# ARE_adaptadora_PIC_28pin.net
KiCad netlist of a schematic drawn in EAGLE
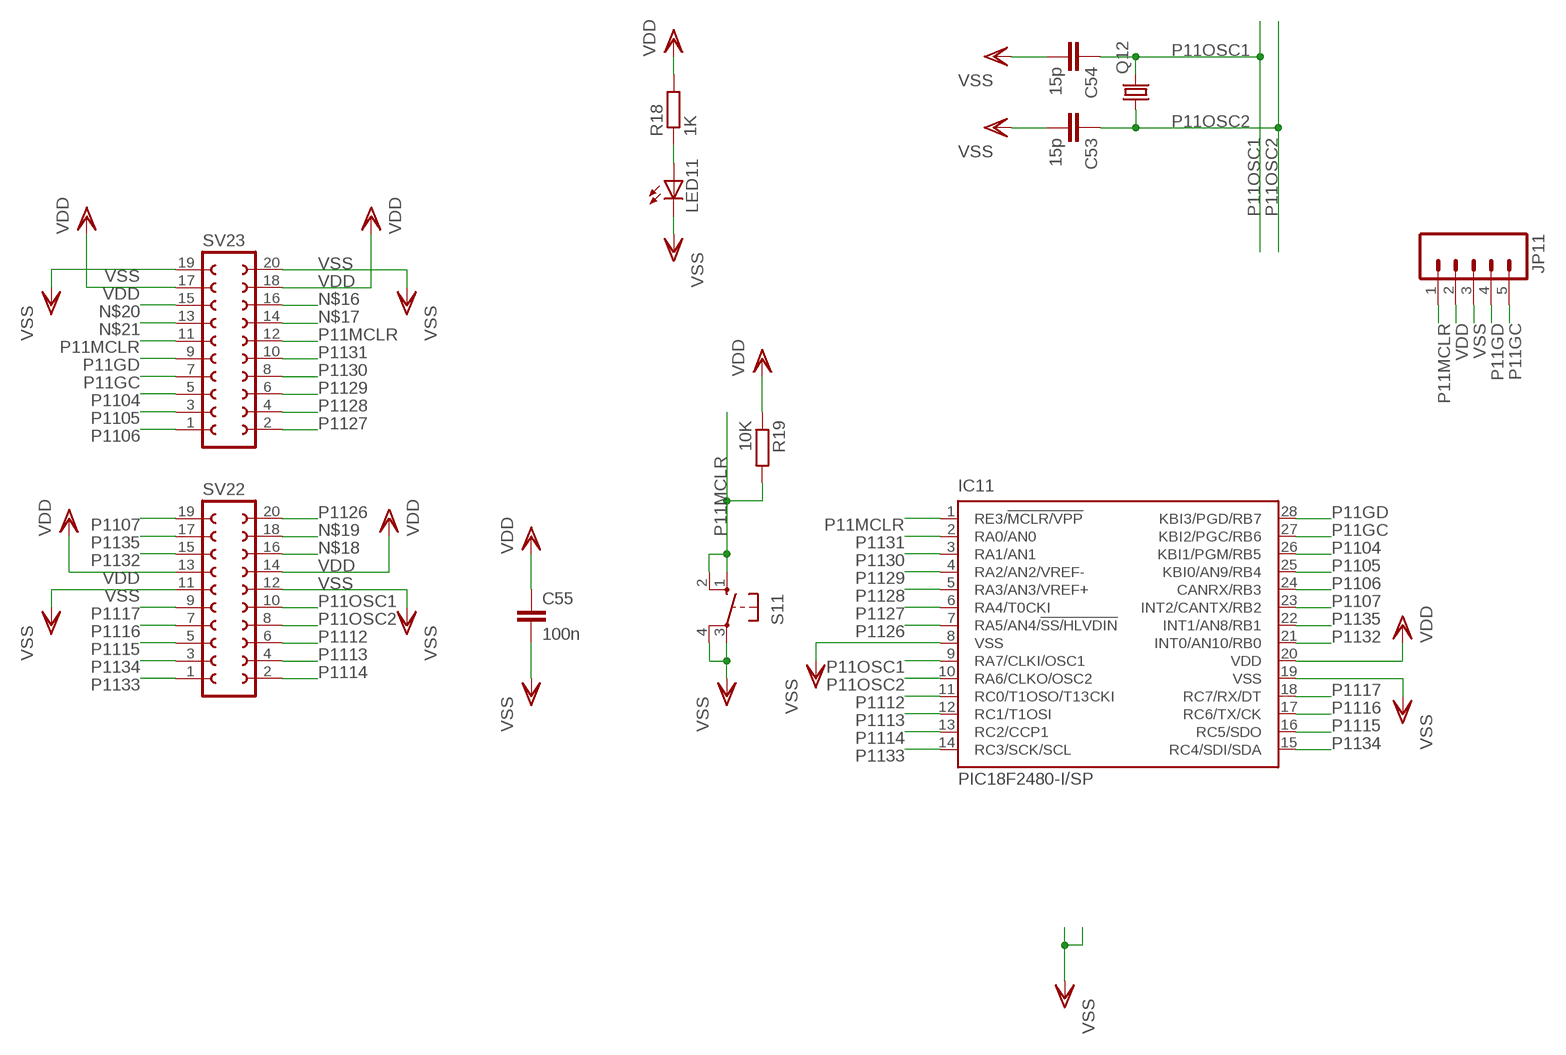
[diagram p0: schematic, sheet 1]

(export (version "E")
  (design (tool "Eeschema 10.0.6"))
  (components
    (comp (ref "C53")
      (value "15p")
      (footprint "eagle-import:C0805")
      (libsource (lib "eagle-import") (part "C-EUC0805"))
    )
    (comp (ref "C54")
      (value "15p")
      (footprint "eagle-import:C0805")
      (libsource (lib "eagle-import") (part "C-EUC0805"))
    )
    (comp (ref "C55")
      (value "100n")
      (footprint "eagle-import:C0805")
      (libsource (lib "eagle-import") (part "C-EUC0805"))
    )
    (comp (ref "IC11")
      (value "PIC18F2480-I/SP")
      (footprint "eagle-import:DIL28-3")
      (fields (field (name "MF") "MICROCHIP"))
      (libsource (lib "eagle-import") (part "PIC18F280-I/SP4"))
    )
    (comp (ref "JP11")
      (value "M05PTH")
      (footprint "eagle-import:1X05")
      (libsource (lib "eagle-import") (part "M05PTH"))
    )
    (comp (ref "LED11")
      (value "LED3MM")
      (footprint "eagle-import:LED3MM")
      (libsource (lib "eagle-import") (part "LED3MM"))
    )
    (comp (ref "Q12")
      (value "CRYSTALHC18U-V")
      (footprint "eagle-import:HC18U-V")
      (libsource (lib "eagle-import") (part "CRYSTALHC18U-V"))
    )
    (comp (ref "R18")
      (value "1K")
      (footprint "eagle-import:R0805")
      (libsource (lib "eagle-import") (part "R-EU_R0805"))
    )
    (comp (ref "R19")
      (value "10K")
      (footprint "eagle-import:R0805")
      (libsource (lib "eagle-import") (part "R-EU_R0805"))
    )
    (comp (ref "S11")
      (value "10-XX")
      (footprint "eagle-import:B3F-10XX")
      (fields
        (field (name "MPN") "B3F-1000")
        (field (name "MPN_1") "B3F-1000")
        (field (name "OC_FARNELL") "176432")
        (field (name "OC_NEWARK") "36M3542")
      )
      (libsource (lib "eagle-import") (part "10-XX"))
    )
    (comp (ref "SV22")
      (value "FE10-2W")
      (footprint "eagle-import:FE10-2W")
      (libsource (lib "eagle-import") (part "FE10-2W"))
    )
    (comp (ref "SV23")
      (value "FE10-2W")
      (footprint "eagle-import:FE10-2W")
      (fields (field (name "OC_FARNELL") "unknown") (field (name "OC_NEWARK") "unknown"))
      (libsource (lib "eagle-import") (part "FE10-2W"))
    )
  )
  (nets
    (net (code "1") (name "/N$16") (class "Default")
      (node (ref "SV23") (pin "16") (pinfunction "16_16") (pintype "passive"))
    )
    (net (code "2") (name "/N$17") (class "Default")
      (node (ref "SV23") (pin "14") (pinfunction "14_14") (pintype "passive"))
    )
    (net (code "3") (name "/N$18") (class "Default")
      (node (ref "SV22") (pin "16") (pinfunction "16_16") (pintype "passive"))
    )
    (net (code "4") (name "/N$19") (class "Default")
      (node (ref "SV22") (pin "18") (pinfunction "18_18") (pintype "passive"))
    )
    (net (code "5") (name "/N$20") (class "Default")
      (node (ref "SV23") (pin "15") (pinfunction "15_15") (pintype "passive"))
    )
    (net (code "6") (name "/N$21") (class "Default")
      (node (ref "SV23") (pin "13") (pinfunction "13_13") (pintype "passive"))
    )
    (net (code "7") (name "/P11GC") (class "Default")
      (node (ref "IC11") (pin "27") (pinfunction "KBI2/PGC/RB6_27") (pintype "bidirectional"))
      (node (ref "JP11") (pin "5") (pinfunction "5_5") (pintype "passive"))
      (node (ref "SV23") (pin "7") (pinfunction "7_7") (pintype "passive"))
    )
    (net (code "8") (name "/P11GD") (class "Default")
      (node (ref "IC11") (pin "28") (pinfunction "KBI3/PGD/RB7_28") (pintype "bidirectional"))
      (node (ref "JP11") (pin "4") (pinfunction "4_4") (pintype "passive"))
      (node (ref "SV23") (pin "9") (pinfunction "9_9") (pintype "passive"))
    )
    (net (code "9") (name "/P11MCLR") (class "Default")
      (node (ref "IC11") (pin "1") (pinfunction "RE3/~{MCLR/VPP}_1") (pintype "input"))
      (node (ref "JP11") (pin "1") (pinfunction "1_1") (pintype "passive"))
      (node (ref "R19") (pin "2") (pinfunction "2_2") (pintype "passive"))
      (node (ref "S11") (pin "1") (pinfunction "S_1") (pintype "passive"))
      (node (ref "S11") (pin "2") (pinfunction "S1_2") (pintype "passive"))
      (node (ref "SV23") (pin "11") (pinfunction "11_11") (pintype "passive"))
      (node (ref "SV23") (pin "12") (pinfunction "12_12") (pintype "passive"))
    )
    (net (code "10") (name "/P11OSC1") (class "Default")
      (node (ref "C54") (pin "1") (pinfunction "1_1") (pintype "passive"))
      (node (ref "IC11") (pin "9") (pinfunction "RA7/CLKI/OSC1_9") (pintype "input"))
      (node (ref "Q12") (pin "2") (pinfunction "2_2") (pintype "passive"))
      (node (ref "SV22") (pin "10") (pinfunction "10_10") (pintype "passive"))
    )
    (net (code "11") (name "/P11OSC2") (class "Default")
      (node (ref "C53") (pin "1") (pinfunction "1_1") (pintype "passive"))
      (node (ref "IC11") (pin "10") (pinfunction "RA6/CLKO/OSC2_10") (pintype "output"))
      (node (ref "Q12") (pin "1") (pinfunction "1_1") (pintype "passive"))
      (node (ref "SV22") (pin "8") (pinfunction "8_8") (pintype "passive"))
    )
    (net (code "12") (name "/P1104") (class "Default")
      (node (ref "IC11") (pin "26") (pinfunction "KBI1/PGM/RB5_26") (pintype "bidirectional"))
      (node (ref "SV23") (pin "5") (pinfunction "5_5") (pintype "passive"))
    )
    (net (code "13") (name "/P1105") (class "Default")
      (node (ref "IC11") (pin "25") (pinfunction "KBI0/AN9/RB4_25") (pintype "bidirectional"))
      (node (ref "SV23") (pin "3") (pinfunction "3_3") (pintype "passive"))
    )
    (net (code "14") (name "/P1106") (class "Default")
      (node (ref "IC11") (pin "24") (pinfunction "CANRX/RB3_24") (pintype "bidirectional"))
      (node (ref "SV23") (pin "1") (pinfunction "1_1") (pintype "passive"))
    )
    (net (code "15") (name "/P1107") (class "Default")
      (node (ref "IC11") (pin "23") (pinfunction "INT2/CANTX/RB2_23") (pintype "bidirectional"))
      (node (ref "SV22") (pin "19") (pinfunction "19_19") (pintype "passive"))
    )
    (net (code "16") (name "/P1112") (class "Default")
      (node (ref "IC11") (pin "11") (pinfunction "RC0/T1OSO/T13CKI_11") (pintype "bidirectional"))
      (node (ref "SV22") (pin "6") (pinfunction "6_6") (pintype "passive"))
    )
    (net (code "17") (name "/P1113") (class "Default")
      (node (ref "IC11") (pin "12") (pinfunction "RC1/T1OSI_12") (pintype "bidirectional"))
      (node (ref "SV22") (pin "4") (pinfunction "4_4") (pintype "passive"))
    )
    (net (code "18") (name "/P1114") (class "Default")
      (node (ref "IC11") (pin "13") (pinfunction "RC2/CCP1_13") (pintype "bidirectional"))
      (node (ref "SV22") (pin "2") (pinfunction "2_2") (pintype "passive"))
    )
    (net (code "19") (name "/P1115") (class "Default")
      (node (ref "IC11") (pin "16") (pinfunction "RC5/SDO_16") (pintype "bidirectional"))
      (node (ref "SV22") (pin "5") (pinfunction "5_5") (pintype "passive"))
    )
    (net (code "20") (name "/P1116") (class "Default")
      (node (ref "IC11") (pin "17") (pinfunction "RC6/TX/CK_17") (pintype "bidirectional"))
      (node (ref "SV22") (pin "7") (pinfunction "7_7") (pintype "passive"))
    )
    (net (code "21") (name "/P1117") (class "Default")
      (node (ref "IC11") (pin "18") (pinfunction "RC7/RX/DT_18") (pintype "bidirectional"))
      (node (ref "SV22") (pin "9") (pinfunction "9_9") (pintype "passive"))
    )
    (net (code "22") (name "/P1126") (class "Default")
      (node (ref "IC11") (pin "7") (pinfunction "RA5/AN4/~{SS/HLVDIN}_7") (pintype "bidirectional"))
      (node (ref "SV22") (pin "20") (pinfunction "20_20") (pintype "passive"))
    )
    (net (code "23") (name "/P1127") (class "Default")
      (node (ref "IC11") (pin "6") (pinfunction "RA4/T0CKI_6") (pintype "bidirectional"))
      (node (ref "SV23") (pin "2") (pinfunction "2_2") (pintype "passive"))
    )
    (net (code "24") (name "/P1128") (class "Default")
      (node (ref "IC11") (pin "5") (pinfunction "RA3/AN3/VREF+_5") (pintype "bidirectional"))
      (node (ref "SV23") (pin "4") (pinfunction "4_4") (pintype "passive"))
    )
    (net (code "25") (name "/P1129") (class "Default")
      (node (ref "IC11") (pin "4") (pinfunction "RA2/AN2/VREF-_4") (pintype "bidirectional"))
      (node (ref "SV23") (pin "6") (pinfunction "6_6") (pintype "passive"))
    )
    (net (code "26") (name "/P1130") (class "Default")
      (node (ref "IC11") (pin "3") (pinfunction "RA1/AN1_3") (pintype "bidirectional"))
      (node (ref "SV23") (pin "8") (pinfunction "8_8") (pintype "passive"))
    )
    (net (code "27") (name "/P1131") (class "Default")
      (node (ref "IC11") (pin "2") (pinfunction "RA0/AN0_2") (pintype "bidirectional"))
      (node (ref "SV23") (pin "10") (pinfunction "10_10") (pintype "passive"))
    )
    (net (code "28") (name "/P1132") (class "Default")
      (node (ref "IC11") (pin "21") (pinfunction "INT0/AN10/RB0_21") (pintype "bidirectional"))
      (node (ref "SV22") (pin "15") (pinfunction "15_15") (pintype "passive"))
    )
    (net (code "29") (name "/P1133") (class "Default")
      (node (ref "IC11") (pin "14") (pinfunction "RC3/SCK/SCL_14") (pintype "bidirectional"))
      (node (ref "SV22") (pin "1") (pinfunction "1_1") (pintype "passive"))
    )
    (net (code "30") (name "/P1134") (class "Default")
      (node (ref "IC11") (pin "15") (pinfunction "RC4/SDI/SDA_15") (pintype "bidirectional"))
      (node (ref "SV22") (pin "3") (pinfunction "3_3") (pintype "passive"))
    )
    (net (code "31") (name "/P1135") (class "Default")
      (node (ref "IC11") (pin "22") (pinfunction "INT1/AN8/RB1_22") (pintype "bidirectional"))
      (node (ref "SV22") (pin "17") (pinfunction "17_17") (pintype "passive"))
    )
    (net (code "32") (name "Net-(LED11-PadA)") (class "Default")
      (node (ref "LED11") (pin "A") (pinfunction "A_A") (pintype "passive"))
      (node (ref "R18") (pin "1") (pinfunction "1_1") (pintype "passive"))
    )
    (net (code "33") (name "VDD") (class "Default")
      (node (ref "C55") (pin "1") (pinfunction "1_1") (pintype "passive"))
      (node (ref "IC11") (pin "20") (pinfunction "VDD_20") (pintype "power_in"))
      (node (ref "JP11") (pin "2") (pinfunction "2_2") (pintype "passive"))
      (node (ref "R18") (pin "2") (pinfunction "2_2") (pintype "passive"))
      (node (ref "R19") (pin "1") (pinfunction "1_1") (pintype "passive"))
      (node (ref "SV22") (pin "13") (pinfunction "13_13") (pintype "passive"))
      (node (ref "SV22") (pin "14") (pinfunction "14_14") (pintype "passive"))
      (node (ref "SV23") (pin "17") (pinfunction "17_17") (pintype "passive"))
      (node (ref "SV23") (pin "18") (pinfunction "18_18") (pintype "passive"))
    )
    (net (code "34") (name "VSS") (class "Default")
      (node (ref "C53") (pin "2") (pinfunction "2_2") (pintype "passive"))
      (node (ref "C54") (pin "2") (pinfunction "2_2") (pintype "passive"))
      (node (ref "C55") (pin "2") (pinfunction "2_2") (pintype "passive"))
      (node (ref "IC11") (pin "19") (pinfunction "VSS_19") (pintype "power_in"))
      (node (ref "IC11") (pin "8") (pinfunction "VSS_8") (pintype "power_in"))
      (node (ref "JP11") (pin "3") (pinfunction "3_3") (pintype "passive"))
      (node (ref "LED11") (pin "K") (pinfunction "C_K") (pintype "passive"))
      (node (ref "S11") (pin "3") (pinfunction "P_3") (pintype "passive"))
      (node (ref "S11") (pin "4") (pinfunction "P1_4") (pintype "passive"))
      (node (ref "SV22") (pin "11") (pinfunction "11_11") (pintype "passive"))
      (node (ref "SV22") (pin "12") (pinfunction "12_12") (pintype "passive"))
      (node (ref "SV23") (pin "19") (pinfunction "19_19") (pintype "passive"))
      (node (ref "SV23") (pin "20") (pinfunction "20_20") (pintype "passive"))
    )
  )
)
